# usb.net
KiCad netlist of a schematic drawn in Altium Designer
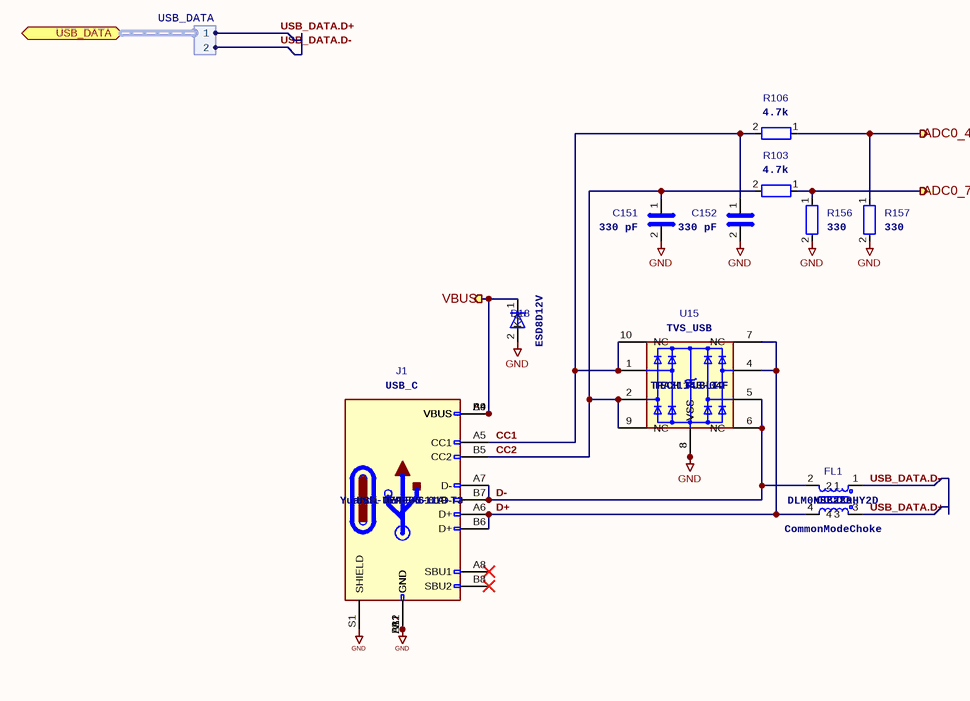
[diagram p0: usb.SchDoc]

(export (version "E")
  (design (tool "Eeschema 10.0.6"))
  (components
    (comp (ref "C151")
      (value "330 pF")
      (footprint "C_0201_0603Metric")
      (fields (field (name "PART NUMBER") "GRM0335C1E331JA01D") (field (name "MANUFACTURER") "Murata"))
      (libsource (lib "Device") (part "C"))
    )
    (comp (ref "C152")
      (value "330 pF")
      (footprint "C_0201_0603Metric")
      (fields (field (name "PART NUMBER") "GRM0335C1E331JA01D") (field (name "MANUFACTURER") "Murata"))
      (libsource (lib "Device") (part "C"))
    )
    (comp (ref "D18")
      (value "TVS")
      (footprint "TSLP-2-19")
      (fields (field (name "MANUFACTURER") "MDD") (field (name "PART NUMBER") "ESD8D12V"))
      (libsource (lib "Device") (part "D_Zener"))
    )
    (comp (ref "FL1")
      (value "CommonModeChoke")
      (footprint "L_CommonModeChoke_Murata_DLM0NS")
      (fields (field (name "MANUFACTURER") "Murata") (field (name "PART NUMBER") "DLM0NSB280HY2D"))
      (libsource (lib "Device") (part "Filter_EMI_CommonMode"))
    )
    (comp (ref "J1")
      (value "USB_C")
      (footprint "USB_C_Receptacle_HRO_TYPE-C-31-M-12")
      (fields
        (field (name "MANUFACTURER") "DEALON")
        (field (name "PART NUMBER") "USB-TYPE-C-019")
        (field (name "SUBSTITUTION") "Yuandi TYPE-611A-T3")
      )
      (libsource (lib "Connector") (part "USB_C_Receptacle_USB2.0_16P"))
    )
    (comp (ref "R103")
      (value "4.7k")
      (footprint "R_0201_0603Metric")
      (fields (field (name "MANUFACTURER") "Yageo") (field (name "PART NUMBER") "RC0201FR-074K7L"))
      (libsource (lib "Device") (part "R"))
    )
    (comp (ref "R106")
      (value "4.7k")
      (footprint "R_0201_0603Metric")
      (fields (field (name "MANUFACTURER") "Yageo") (field (name "PART NUMBER") "RC0201FR-074K7L"))
      (libsource (lib "Device") (part "R"))
    )
    (comp (ref "R156")
      (value "330")
      (footprint "R_0201_0603Metric")
      (fields (field (name "MANUFACTURER") "Yageo") (field (name "PART NUMBER") "RC0201JR-07330RL"))
      (libsource (lib "") (part "R_1"))
    )
    (comp (ref "R157")
      (value "330")
      (footprint "R_0201_0603Metric")
      (fields (field (name "MANUFACTURER") "Yageo") (field (name "PART NUMBER") "RC0201JR-07330RL"))
      (libsource (lib "") (part "R_1"))
    )
    (comp (ref "U15")
      (value "TVS_USB")
      (footprint "Diodes_UDFN-10_1.0x2.5mm_P0.5mm")
      (fields (field (name "MANUFACTURER") "TECH PUBLIC") (field (name "PART NUMBER") "TPAZ1143-04F"))
      (libsource (lib "Power_Protection") (part "D3V3XA4B10LP"))
    )
  )
  (nets
    (net (code "2") (name "/ADC0_4") (class "Default")
      (node (ref "R106") (pin "1") (pinfunction "1_1") (pintype "passive"))
      (node (ref "R157") (pin "1") (pinfunction "1_1") (pintype "passive"))
    )
    (net (code "3") (name "/ADC0_7") (class "Default")
      (node (ref "R103") (pin "1") (pinfunction "1_1") (pintype "passive"))
      (node (ref "R156") (pin "1") (pinfunction "1_1") (pintype "passive"))
    )
    (net (code "4") (name "/CC1") (class "Default")
      (node (ref "C152") (pin "1") (pinfunction "1_1") (pintype "passive"))
      (node (ref "J1") (pin "A5") (pinfunction "CC1_A5") (pintype "passive"))
      (node (ref "R106") (pin "2") (pinfunction "2_2") (pintype "passive"))
      (node (ref "U15") (pin "1") (pinfunction "1_1") (pintype "passive"))
      (node (ref "U15") (pin "10") (pinfunction "NC_10") (pintype "passive"))
    )
    (net (code "5") (name "/CC2") (class "Default")
      (node (ref "C151") (pin "1") (pinfunction "1_1") (pintype "passive"))
      (node (ref "J1") (pin "B5") (pinfunction "CC2_B5") (pintype "passive"))
      (node (ref "R103") (pin "2") (pinfunction "2_2") (pintype "passive"))
      (node (ref "U15") (pin "2") (pinfunction "2_2") (pintype "passive"))
      (node (ref "U15") (pin "9") (pinfunction "NC_9") (pintype "passive"))
    )
    (net (code "6") (name "/D+") (class "Default")
      (node (ref "FL1") (pin "4") (pinfunction "4_4") (pintype "passive"))
      (node (ref "J1") (pin "A6") (pinfunction "D+_A6") (pintype "passive"))
      (node (ref "J1") (pin "B6") (pinfunction "D+_B6") (pintype "passive"))
      (node (ref "U15") (pin "4") (pinfunction "4_4") (pintype "passive"))
      (node (ref "U15") (pin "7") (pinfunction "NC_7") (pintype "passive"))
    )
    (net (code "7") (name "/D-") (class "Default")
      (node (ref "FL1") (pin "2") (pinfunction "2_2") (pintype "passive"))
      (node (ref "J1") (pin "A7") (pinfunction "D-_A7") (pintype "passive"))
      (node (ref "J1") (pin "B7") (pinfunction "D-_B7") (pintype "passive"))
      (node (ref "U15") (pin "5") (pinfunction "5_5") (pintype "passive"))
      (node (ref "U15") (pin "6") (pinfunction "NC_6") (pintype "passive"))
    )
    (net (code "8") (name "/USB_DATA.D+") (class "Default")
      (node (ref "FL1") (pin "3") (pinfunction "3_3") (pintype "passive"))
    )
    (net (code "9") (name "/USB_DATA.D-") (class "Default")
      (node (ref "FL1") (pin "1") (pinfunction "1_1") (pintype "passive"))
    )
    (net (code "10") (name "/VBUS") (class "Default")
      (node (ref "D18") (pin "1") (pinfunction "K_1") (pintype "passive"))
      (node (ref "J1") (pin "A4") (pinfunction "VBUS_A4") (pintype "passive"))
      (node (ref "J1") (pin "A9") (pinfunction "VBUS_A9") (pintype "passive"))
      (node (ref "J1") (pin "B4") (pinfunction "VBUS_B4") (pintype "passive"))
      (node (ref "J1") (pin "B9") (pinfunction "VBUS_B9") (pintype "passive"))
    )
    (net (code "12") (name "GND") (class "Default")
      (node (ref "C151") (pin "2") (pinfunction "2_2") (pintype "passive"))
      (node (ref "C152") (pin "2") (pinfunction "2_2") (pintype "passive"))
      (node (ref "D18") (pin "2") (pinfunction "A_2") (pintype "passive"))
      (node (ref "J1") (pin "A1") (pinfunction "GND_A1") (pintype "passive"))
      (node (ref "J1") (pin "A12") (pinfunction "GND_A12") (pintype "passive"))
      (node (ref "J1") (pin "B1") (pinfunction "GND_B1") (pintype "passive"))
      (node (ref "J1") (pin "B12") (pinfunction "GND_B12") (pintype "passive"))
      (node (ref "J1") (pin "S1") (pinfunction "SHIELD_S1") (pintype "passive"))
      (node (ref "R156") (pin "2") (pinfunction "2_2") (pintype "passive"))
      (node (ref "R157") (pin "2") (pinfunction "2_2") (pintype "passive"))
      (node (ref "U15") (pin "3") (pinfunction "VSS_3") (pintype "passive"))
      (node (ref "U15") (pin "8") (pinfunction "VSS_8") (pintype "passive"))
    )
    (net (code "13") (name "unconnected-(J1-SBU1-PadA8)") (class "Default")
      (node (ref "J1") (pin "A8") (pinfunction "SBU1_A8") (pintype "passive+no_connect"))
    )
    (net (code "14") (name "unconnected-(J1-SBU2-PadB8)") (class "Default")
      (node (ref "J1") (pin "B8") (pinfunction "SBU2_B8") (pintype "passive+no_connect"))
    )
  )
)
